# Power.net
KiCad netlist of a schematic drawn in Altium Designer
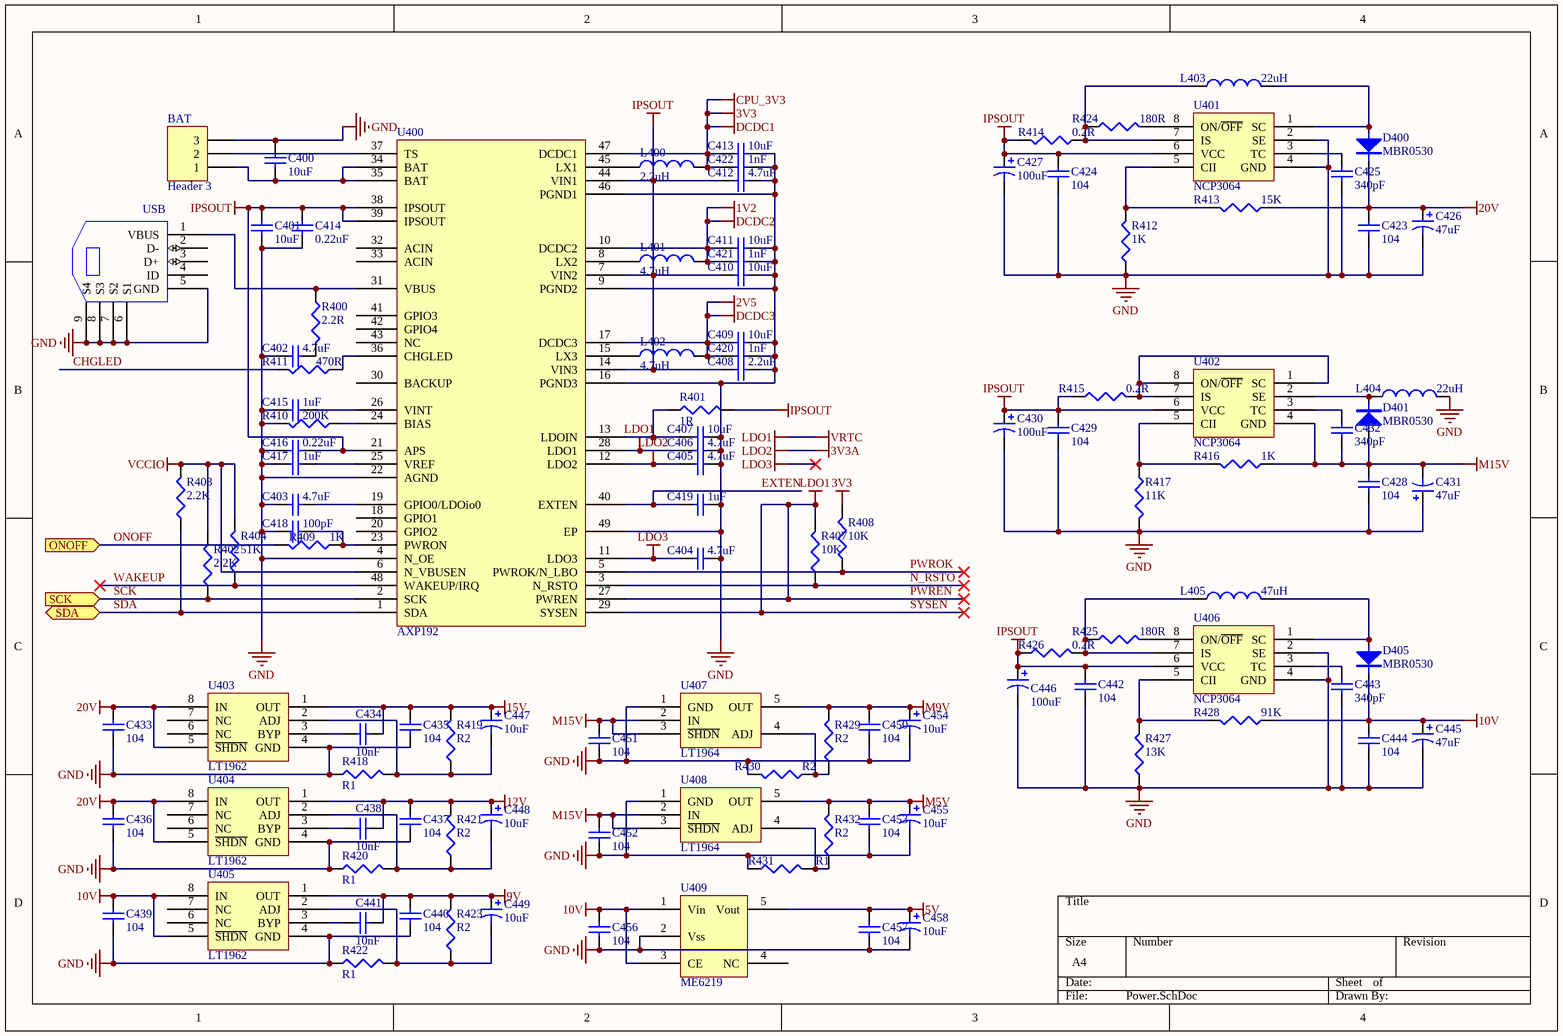
[diagram p0: Power.SchDoc]

(export (version "E")
  (design (tool "Eeschema 10.0.6"))
  (components
    (comp (ref "BAT")
      (value "Header 3")
      (footprint "LBAT")
      (description "Header, 3-Pin")
      (fields (field (name "PUBLISHER") "Altium Limited"))
      (libsource (lib "Miscellaneous Connectors") (part "Header 3"))
    )
    (comp (ref "C400")
      (value "10uF")
      (description "Capacitor (Semiconductor SIM Model)")
      (fields (field (name "PUBLISHER") "Altium Limited"))
      (libsource (lib "Miscellaneous Devices") (part "Cap Semi"))
    )
    (comp (ref "C401")
      (value "10uF")
      (description "Capacitor (Semiconductor SIM Model)")
      (fields (field (name "PUBLISHER") "Altium Limited"))
      (libsource (lib "Miscellaneous Devices") (part "Cap Semi"))
    )
    (comp (ref "C402")
      (value "4.7uF")
      (description "Capacitor (Semiconductor SIM Model)")
      (fields (field (name "PUBLISHER") "Altium Limited"))
      (libsource (lib "Miscellaneous Devices") (part "Cap Semi"))
    )
    (comp (ref "C403")
      (value "4.7uF")
      (description "Capacitor (Semiconductor SIM Model)")
      (fields (field (name "PUBLISHER") "Altium Limited"))
      (libsource (lib "Miscellaneous Devices") (part "Cap Semi"))
    )
    (comp (ref "C404")
      (value "4.7uF")
      (description "Capacitor (Semiconductor SIM Model)")
      (fields (field (name "PUBLISHER") "Altium Limited"))
      (libsource (lib "Miscellaneous Devices") (part "Cap Semi"))
    )
    (comp (ref "C405")
      (value "4.7uF")
      (description "Capacitor (Semiconductor SIM Model)")
      (fields (field (name "PUBLISHER") "Altium Limited"))
      (libsource (lib "Miscellaneous Devices") (part "Cap Semi"))
    )
    (comp (ref "C406")
      (value "4.7uF")
      (description "Capacitor (Semiconductor SIM Model)")
      (fields (field (name "PUBLISHER") "Altium Limited"))
      (libsource (lib "Miscellaneous Devices") (part "Cap Semi"))
    )
    (comp (ref "C407")
      (value "10uF")
      (description "Capacitor (Semiconductor SIM Model)")
      (fields (field (name "PUBLISHER") "Altium Limited"))
      (libsource (lib "Miscellaneous Devices") (part "Cap Semi"))
    )
    (comp (ref "C408")
      (value "2.2uF")
      (description "Capacitor (Semiconductor SIM Model)")
      (fields (field (name "PUBLISHER") "Altium Limited"))
      (libsource (lib "Miscellaneous Devices") (part "Cap Semi"))
    )
    (comp (ref "C409")
      (value "10uF")
      (description "Capacitor (Semiconductor SIM Model)")
      (fields (field (name "PUBLISHER") "Altium Limited"))
      (libsource (lib "Miscellaneous Devices") (part "Cap Semi"))
    )
    (comp (ref "C410")
      (value "10uF")
      (description "Capacitor (Semiconductor SIM Model)")
      (fields (field (name "PUBLISHER") "Altium Limited"))
      (libsource (lib "Miscellaneous Devices") (part "Cap Semi"))
    )
    (comp (ref "C411")
      (value "10uF")
      (description "Capacitor (Semiconductor SIM Model)")
      (fields (field (name "PUBLISHER") "Altium Limited"))
      (libsource (lib "Miscellaneous Devices") (part "Cap Semi"))
    )
    (comp (ref "C412")
      (value "4.7uF")
      (description "Capacitor (Semiconductor SIM Model)")
      (fields (field (name "PUBLISHER") "Altium Limited"))
      (libsource (lib "Miscellaneous Devices") (part "Cap Semi"))
    )
    (comp (ref "C413")
      (value "10uF")
      (description "Capacitor (Semiconductor SIM Model)")
      (fields (field (name "PUBLISHER") "Altium Limited"))
      (libsource (lib "Miscellaneous Devices") (part "Cap Semi"))
    )
    (comp (ref "C414")
      (value "0.22uF")
      (footprint "C0603")
      (description "Capacitor (Semiconductor SIM Model)")
      (fields (field (name "PUBLISHER") "Altium Limited"))
      (libsource (lib "Miscellaneous Devices") (part "Cap Semi"))
    )
    (comp (ref "C415")
      (value "1uF")
      (footprint "C0603")
      (description "Capacitor (Semiconductor SIM Model)")
      (fields (field (name "PUBLISHER") "Altium Limited"))
      (libsource (lib "Miscellaneous Devices") (part "Cap Semi"))
    )
    (comp (ref "C416")
      (value "0.22uF")
      (footprint "C0603")
      (description "Capacitor (Semiconductor SIM Model)")
      (fields (field (name "PUBLISHER") "Altium Limited"))
      (libsource (lib "Miscellaneous Devices") (part "Cap Semi"))
    )
    (comp (ref "C417")
      (value "1uF")
      (footprint "C0603")
      (description "Capacitor (Semiconductor SIM Model)")
      (fields (field (name "PUBLISHER") "Altium Limited"))
      (libsource (lib "Miscellaneous Devices") (part "Cap Semi"))
    )
    (comp (ref "C418")
      (value "100pF")
      (footprint "C0603")
      (description "Capacitor (Semiconductor SIM Model)")
      (fields (field (name "PUBLISHER") "Altium Limited"))
      (libsource (lib "Miscellaneous Devices") (part "Cap Semi"))
    )
    (comp (ref "C419")
      (value "1uF")
      (footprint "C0603")
      (description "Capacitor (Semiconductor SIM Model)")
      (fields (field (name "PUBLISHER") "Altium Limited"))
      (libsource (lib "Miscellaneous Devices") (part "Cap Semi"))
    )
    (comp (ref "C420")
      (value "1nF")
      (footprint "C0603")
      (description "Capacitor (Semiconductor SIM Model)")
      (fields (field (name "PUBLISHER") "Altium Limited"))
      (libsource (lib "Miscellaneous Devices") (part "Cap Semi"))
    )
    (comp (ref "C421")
      (value "1nF")
      (footprint "C0603")
      (description "Capacitor (Semiconductor SIM Model)")
      (fields (field (name "PUBLISHER") "Altium Limited"))
      (libsource (lib "Miscellaneous Devices") (part "Cap Semi"))
    )
    (comp (ref "C422")
      (value "1nF")
      (footprint "C0603")
      (description "Capacitor (Semiconductor SIM Model)")
      (fields (field (name "PUBLISHER") "Altium Limited"))
      (libsource (lib "Miscellaneous Devices") (part "Cap Semi"))
    )
    (comp (ref "C423")
      (value "104")
      (footprint "C0402")
      (description "Capacitor (Semiconductor SIM Model)")
      (fields (field (name "PUBLISHER") "Altium Limited"))
      (libsource (lib "Miscellaneous Devices") (part "Cap Semi"))
    )
    (comp (ref "C424")
      (value "104")
      (footprint "C0402")
      (description "Capacitor (Semiconductor SIM Model)")
      (fields (field (name "PUBLISHER") "Altium Limited"))
      (libsource (lib "Miscellaneous Devices") (part "Cap Semi"))
    )
    (comp (ref "C425")
      (value "340pF")
      (footprint "C0402")
      (description "Capacitor (Semiconductor SIM Model)")
      (fields (field (name "PUBLISHER") "Altium Limited"))
      (libsource (lib "Miscellaneous Devices") (part "Cap Semi"))
    )
    (comp (ref "C426")
      (value "47uF")
      (footprint "7343")
      (description "Polarized Capacitor (Radial)")
      (fields (field (name "PUBLISHER") "Altium Limited"))
      (libsource (lib "Miscellaneous Devices") (part "Cap Pol1"))
    )
    (comp (ref "C427")
      (value "100uF")
      (footprint "C0805")
      (description "Polarized Capacitor (Radial)")
      (fields (field (name "PUBLISHER") "Altium Limited"))
      (libsource (lib "Miscellaneous Devices") (part "Cap Pol1"))
    )
    (comp (ref "C428")
      (value "104")
      (footprint "C0402")
      (description "Capacitor (Semiconductor SIM Model)")
      (fields (field (name "PUBLISHER") "Altium Limited"))
      (libsource (lib "Miscellaneous Devices") (part "Cap Semi"))
    )
    (comp (ref "C429")
      (value "104")
      (footprint "C0402")
      (description "Capacitor (Semiconductor SIM Model)")
      (fields (field (name "PUBLISHER") "Altium Limited"))
      (libsource (lib "Miscellaneous Devices") (part "Cap Semi"))
    )
    (comp (ref "C430")
      (value "100uF")
      (footprint "C0805")
      (description "Polarized Capacitor (Radial)")
      (fields (field (name "PUBLISHER") "Altium Limited"))
      (libsource (lib "Miscellaneous Devices") (part "Cap Pol1"))
    )
    (comp (ref "C431")
      (value "47uF")
      (footprint "7343")
      (description "Polarized Capacitor (Radial)")
      (fields (field (name "PUBLISHER") "Altium Limited"))
      (libsource (lib "Miscellaneous Devices") (part "Cap Pol1"))
    )
    (comp (ref "C432")
      (value "340pF")
      (description "Capacitor (Semiconductor SIM Model)")
      (fields (field (name "PUBLISHER") "Altium Limited"))
      (libsource (lib "Miscellaneous Devices") (part "Cap Semi"))
    )
    (comp (ref "C433")
      (value "104")
      (footprint "C0402")
      (description "Capacitor (Semiconductor SIM Model)")
      (fields (field (name "PUBLISHER") "Altium Limited"))
      (libsource (lib "Miscellaneous Devices") (part "Cap Semi"))
    )
    (comp (ref "C434")
      (value "10nF")
      (footprint "C0402")
      (description "Capacitor (Semiconductor SIM Model)")
      (fields (field (name "PUBLISHER") "Altium Limited"))
      (libsource (lib "Miscellaneous Devices") (part "Cap Semi"))
    )
    (comp (ref "C435")
      (value "104")
      (footprint "C0402")
      (description "Capacitor (Semiconductor SIM Model)")
      (fields (field (name "PUBLISHER") "Altium Limited"))
      (libsource (lib "Miscellaneous Devices") (part "Cap Semi"))
    )
    (comp (ref "C436")
      (value "104")
      (footprint "C0402")
      (description "Capacitor (Semiconductor SIM Model)")
      (fields (field (name "PUBLISHER") "Altium Limited"))
      (libsource (lib "Miscellaneous Devices") (part "Cap Semi"))
    )
    (comp (ref "C437")
      (value "104")
      (footprint "C0402")
      (description "Capacitor (Semiconductor SIM Model)")
      (fields (field (name "PUBLISHER") "Altium Limited"))
      (libsource (lib "Miscellaneous Devices") (part "Cap Semi"))
    )
    (comp (ref "C438")
      (value "10nF")
      (footprint "C0402")
      (description "Capacitor (Semiconductor SIM Model)")
      (fields (field (name "PUBLISHER") "Altium Limited"))
      (libsource (lib "Miscellaneous Devices") (part "Cap Semi"))
    )
    (comp (ref "C439")
      (value "104")
      (footprint "C0402")
      (description "Capacitor (Semiconductor SIM Model)")
      (fields (field (name "PUBLISHER") "Altium Limited"))
      (libsource (lib "Miscellaneous Devices") (part "Cap Semi"))
    )
    (comp (ref "C440")
      (value "104")
      (footprint "C0402")
      (description "Capacitor (Semiconductor SIM Model)")
      (fields (field (name "PUBLISHER") "Altium Limited"))
      (libsource (lib "Miscellaneous Devices") (part "Cap Semi"))
    )
    (comp (ref "C441")
      (value "10nF")
      (footprint "C0402")
      (description "Capacitor (Semiconductor SIM Model)")
      (fields (field (name "PUBLISHER") "Altium Limited"))
      (libsource (lib "Miscellaneous Devices") (part "Cap Semi"))
    )
    (comp (ref "C442")
      (value "104")
      (footprint "C0402")
      (description "Capacitor (Semiconductor SIM Model)")
      (fields (field (name "PUBLISHER") "Altium Limited"))
      (libsource (lib "Miscellaneous Devices") (part "Cap Semi"))
    )
    (comp (ref "C443")
      (value "340pF")
      (footprint "C0402")
      (description "Capacitor (Semiconductor SIM Model)")
      (fields (field (name "PUBLISHER") "Altium Limited"))
      (libsource (lib "Miscellaneous Devices") (part "Cap Semi"))
    )
    (comp (ref "C444")
      (value "104")
      (footprint "C0402")
      (description "Capacitor (Semiconductor SIM Model)")
      (fields (field (name "PUBLISHER") "Altium Limited"))
      (libsource (lib "Miscellaneous Devices") (part "Cap Semi"))
    )
    (comp (ref "C445")
      (value "47uF")
      (footprint "7343")
      (description "Polarized Capacitor (Radial)")
      (fields (field (name "PUBLISHER") "Altium Limited"))
      (libsource (lib "Miscellaneous Devices") (part "Cap Pol1"))
    )
    (comp (ref "C446")
      (value "100uF")
      (footprint "C0805")
      (description "Polarized Capacitor (Radial)")
      (fields (field (name "PUBLISHER") "Altium Limited"))
      (libsource (lib "Miscellaneous Devices") (part "Cap Pol1"))
    )
    (comp (ref "C447")
      (value "10uF")
      (footprint "7343")
      (description "Polarized Capacitor (Radial)")
      (fields (field (name "PUBLISHER") "Altium Limited"))
      (libsource (lib "Miscellaneous Devices") (part "Cap Pol1"))
    )
    (comp (ref "C448")
      (value "10uF")
      (footprint "7343")
      (description "Polarized Capacitor (Radial)")
      (fields (field (name "PUBLISHER") "Altium Limited"))
      (libsource (lib "Miscellaneous Devices") (part "Cap Pol1"))
    )
    (comp (ref "C449")
      (value "10uF")
      (footprint "7343")
      (description "Polarized Capacitor (Radial)")
      (fields (field (name "PUBLISHER") "Altium Limited"))
      (libsource (lib "Miscellaneous Devices") (part "Cap Pol1"))
    )
    (comp (ref "C450")
      (value "104")
      (footprint "C0402")
      (description "Capacitor (Semiconductor SIM Model)")
      (fields (field (name "PUBLISHER") "Altium Limited"))
      (libsource (lib "Miscellaneous Devices") (part "Cap Semi"))
    )
    (comp (ref "C451")
      (value "104")
      (footprint "C0402")
      (description "Capacitor (Semiconductor SIM Model)")
      (fields (field (name "PUBLISHER") "Altium Limited"))
      (libsource (lib "Miscellaneous Devices") (part "Cap Semi"))
    )
    (comp (ref "C452")
      (value "104")
      (footprint "C0402")
      (description "Capacitor (Semiconductor SIM Model)")
      (fields (field (name "PUBLISHER") "Altium Limited"))
      (libsource (lib "Miscellaneous Devices") (part "Cap Semi"))
    )
    (comp (ref "C453")
      (value "104")
      (footprint "C0402")
      (description "Capacitor (Semiconductor SIM Model)")
      (fields (field (name "PUBLISHER") "Altium Limited"))
      (libsource (lib "Miscellaneous Devices") (part "Cap Semi"))
    )
    (comp (ref "C454")
      (value "10uF")
      (footprint "7343")
      (description "Polarized Capacitor (Radial)")
      (fields (field (name "PUBLISHER") "Altium Limited"))
      (libsource (lib "Miscellaneous Devices") (part "Cap Pol1"))
    )
    (comp (ref "C455")
      (value "10uF")
      (footprint "7343")
      (description "Polarized Capacitor (Radial)")
      (fields (field (name "PUBLISHER") "Altium Limited"))
      (libsource (lib "Miscellaneous Devices") (part "Cap Pol1"))
    )
    (comp (ref "C456")
      (value "104")
      (footprint "C0402")
      (description "Capacitor (Semiconductor SIM Model)")
      (fields (field (name "PUBLISHER") "Altium Limited"))
      (libsource (lib "Miscellaneous Devices") (part "Cap Semi"))
    )
    (comp (ref "C457")
      (value "104")
      (footprint "C0402")
      (description "Capacitor (Semiconductor SIM Model)")
      (fields (field (name "PUBLISHER") "Altium Limited"))
      (libsource (lib "Miscellaneous Devices") (part "Cap Semi"))
    )
    (comp (ref "C458")
      (value "10uF")
      (footprint "7343")
      (description "Polarized Capacitor (Radial)")
      (fields (field (name "PUBLISHER") "Altium Limited"))
      (libsource (lib "Miscellaneous Devices") (part "Cap Pol1"))
    )
    (comp (ref "D400") (value "MBR0530") (footprint "SOD123") (libsource (lib "Schlib1") (part "MBR0530")))
    (comp (ref "D401") (value "MBR0530") (footprint "SOD123") (libsource (lib "Schlib1") (part "MBR0530")))
    (comp (ref "D405") (value "MBR0530") (footprint "SOD123") (libsource (lib "Schlib1") (part "MBR0530")))
    (comp (ref "L400")
      (value "2.2uH")
      (footprint "IND_4X4")
      (description "Inductor")
      (fields (field (name "PUBLISHER") "Altium Limited"))
      (libsource (lib "Miscellaneous Devices") (part "Inductor"))
    )
    (comp (ref "L401")
      (value "4.7uH")
      (footprint "IND_4X4")
      (description "Inductor")
      (fields (field (name "PUBLISHER") "Altium Limited"))
      (libsource (lib "Miscellaneous Devices") (part "Inductor"))
    )
    (comp (ref "L402")
      (value "4.7uH")
      (footprint "IND_4X4")
      (description "Inductor")
      (fields (field (name "PUBLISHER") "Altium Limited"))
      (libsource (lib "Miscellaneous Devices") (part "Inductor"))
    )
    (comp (ref "L403")
      (value "22uH")
      (footprint "IND_4X4")
      (description "Inductor")
      (fields (field (name "PUBLISHER") "Altium Limited"))
      (libsource (lib "Miscellaneous Devices") (part "Inductor"))
    )
    (comp (ref "L404")
      (value "22uH")
      (footprint "IND_4X4")
      (description "Inductor")
      (fields (field (name "PUBLISHER") "Altium Limited"))
      (libsource (lib "Miscellaneous Devices") (part "Inductor"))
    )
    (comp (ref "L405")
      (value "47uH")
      (footprint "IND_4X4")
      (description "Inductor")
      (fields (field (name "PUBLISHER") "Altium Limited"))
      (libsource (lib "Miscellaneous Devices") (part "Inductor"))
    )
    (comp (ref "R400")
      (value "2.2R")
      (footprint "R0603")
      (description "Resistor")
      (fields (field (name "PUBLISHER") "Altium Limited"))
      (libsource (lib "Miscellaneous Devices") (part "Res3"))
    )
    (comp (ref "R401")
      (value "1R")
      (footprint "R0805")
      (description "Resistor")
      (fields (field (name "PUBLISHER") "Altium Limited"))
      (libsource (lib "Miscellaneous Devices") (part "Res3"))
    )
    (comp (ref "R402")
      (value "2.2K")
      (footprint "R0603")
      (description "Resistor")
      (fields (field (name "PUBLISHER") "Altium Limited"))
      (libsource (lib "Miscellaneous Devices") (part "Res3"))
    )
    (comp (ref "R403")
      (value "2.2K")
      (footprint "R0603")
      (description "Resistor")
      (fields (field (name "PUBLISHER") "Altium Limited"))
      (libsource (lib "Miscellaneous Devices") (part "Res3"))
    )
    (comp (ref "R404")
      (value "51K")
      (footprint "R0603")
      (description "Resistor")
      (fields (field (name "PUBLISHER") "Altium Limited"))
      (libsource (lib "Miscellaneous Devices") (part "Res3"))
    )
    (comp (ref "R407")
      (value "10K")
      (footprint "R0603")
      (description "Resistor")
      (fields (field (name "PUBLISHER") "Altium Limited"))
      (libsource (lib "Miscellaneous Devices") (part "Res3"))
    )
    (comp (ref "R408")
      (value "10K")
      (footprint "R0603")
      (description "Resistor")
      (fields (field (name "PUBLISHER") "Altium Limited"))
      (libsource (lib "Miscellaneous Devices") (part "Res3"))
    )
    (comp (ref "R409")
      (value "1K")
      (footprint "R0603")
      (description "Resistor")
      (fields (field (name "PUBLISHER") "Altium Limited"))
      (libsource (lib "Miscellaneous Devices") (part "Res3"))
    )
    (comp (ref "R410")
      (value "200K")
      (footprint "R0603")
      (description "Resistor")
      (fields (field (name "PUBLISHER") "Altium Limited"))
      (libsource (lib "Miscellaneous Devices") (part "Res3"))
    )
    (comp (ref "R411")
      (value "470R")
      (footprint "R0603")
      (description "Resistor")
      (fields (field (name "PUBLISHER") "Altium Limited"))
      (libsource (lib "Miscellaneous Devices") (part "Res3"))
    )
    (comp (ref "R412")
      (value "1K")
      (footprint "R0603")
      (description "Resistor")
      (fields (field (name "PUBLISHER") "Altium Limited"))
      (libsource (lib "Miscellaneous Devices") (part "Res3"))
    )
    (comp (ref "R413")
      (value "15K")
      (footprint "R0603")
      (description "Resistor")
      (fields (field (name "PUBLISHER") "Altium Limited"))
      (libsource (lib "Miscellaneous Devices") (part "Res3"))
    )
    (comp (ref "R414")
      (value "0.2R")
      (footprint "R0805")
      (description "Resistor")
      (fields (field (name "PUBLISHER") "Altium Limited"))
      (libsource (lib "Miscellaneous Devices") (part "Res3"))
    )
    (comp (ref "R415")
      (value "0.2R")
      (footprint "R0805")
      (description "Resistor")
      (fields (field (name "PUBLISHER") "Altium Limited"))
      (libsource (lib "Miscellaneous Devices") (part "Res3"))
    )
    (comp (ref "R416")
      (value "1K")
      (footprint "R0603")
      (description "Resistor")
      (fields (field (name "PUBLISHER") "Altium Limited"))
      (libsource (lib "Miscellaneous Devices") (part "Res3"))
    )
    (comp (ref "R417")
      (value "11K")
      (footprint "R0603")
      (description "Resistor")
      (fields (field (name "PUBLISHER") "Altium Limited"))
      (libsource (lib "Miscellaneous Devices") (part "Res3"))
    )
    (comp (ref "R418")
      (value "R1")
      (footprint "R0603")
      (description "Resistor")
      (fields (field (name "PUBLISHER") "Altium Limited"))
      (libsource (lib "Miscellaneous Devices") (part "Res3"))
    )
    (comp (ref "R419")
      (value "R2")
      (footprint "R0603")
      (description "Resistor")
      (fields (field (name "PUBLISHER") "Altium Limited"))
      (libsource (lib "Miscellaneous Devices") (part "Res3"))
    )
    (comp (ref "R420")
      (value "R1")
      (footprint "R0603")
      (description "Resistor")
      (fields (field (name "PUBLISHER") "Altium Limited"))
      (libsource (lib "Miscellaneous Devices") (part "Res3"))
    )
    (comp (ref "R421")
      (value "R2")
      (footprint "R0603")
      (description "Resistor")
      (fields (field (name "PUBLISHER") "Altium Limited"))
      (libsource (lib "Miscellaneous Devices") (part "Res3"))
    )
    (comp (ref "R422")
      (value "R1")
      (footprint "R0603")
      (description "Resistor")
      (fields (field (name "PUBLISHER") "Altium Limited"))
      (libsource (lib "Miscellaneous Devices") (part "Res3"))
    )
    (comp (ref "R423")
      (value "R2")
      (footprint "R0603")
      (description "Resistor")
      (fields (field (name "PUBLISHER") "Altium Limited"))
      (libsource (lib "Miscellaneous Devices") (part "Res3"))
    )
    (comp (ref "R424")
      (value "180R")
      (footprint "R0603")
      (description "Resistor")
      (fields (field (name "PUBLISHER") "Altium Limited"))
      (libsource (lib "Miscellaneous Devices") (part "Res3"))
    )
    (comp (ref "R425")
      (value "180R")
      (footprint "R0603")
      (description "Resistor")
      (fields (field (name "PUBLISHER") "Altium Limited"))
      (libsource (lib "Miscellaneous Devices") (part "Res3"))
    )
    (comp (ref "R426")
      (value "0.2R")
      (footprint "R0805")
      (description "Resistor")
      (fields (field (name "PUBLISHER") "Altium Limited"))
      (libsource (lib "Miscellaneous Devices") (part "Res3"))
    )
    (comp (ref "R427")
      (value "13K")
      (footprint "R0603")
      (description "Resistor")
      (fields (field (name "PUBLISHER") "Altium Limited"))
      (libsource (lib "Miscellaneous Devices") (part "Res3"))
    )
    (comp (ref "R428")
      (value "91K")
      (footprint "R0603")
      (description "Resistor")
      (fields (field (name "PUBLISHER") "Altium Limited"))
      (libsource (lib "Miscellaneous Devices") (part "Res3"))
    )
    (comp (ref "R429")
      (value "R2")
      (footprint "R0603")
      (description "Resistor")
      (fields (field (name "PUBLISHER") "Altium Limited"))
      (libsource (lib "Miscellaneous Devices") (part "Res3"))
    )
    (comp (ref "R430")
      (value "R2")
      (footprint "R0603")
      (description "Resistor")
      (fields (field (name "PUBLISHER") "Altium Limited"))
      (libsource (lib "Miscellaneous Devices") (part "Res3"))
    )
    (comp (ref "R431")
      (value "R1")
      (footprint "R0603")
      (description "Resistor")
      (fields (field (name "PUBLISHER") "Altium Limited"))
      (libsource (lib "Miscellaneous Devices") (part "Res3"))
    )
    (comp (ref "R432")
      (value "R2")
      (footprint "R0603")
      (description "Resistor")
      (fields (field (name "PUBLISHER") "Altium Limited"))
      (libsource (lib "Miscellaneous Devices") (part "Res3"))
    )
    (comp (ref "U400") (value "AXP192") (footprint "QFN-48") (libsource (lib "Schlib1") (part "AXP192")))
    (comp (ref "U401") (value "NCP3064") (footprint "SOP-8") (libsource (lib "Schlib1") (part "NCP3064")))
    (comp (ref "U402") (value "NCP3064") (footprint "SOP-8") (libsource (lib "Schlib1") (part "NCP3064")))
    (comp (ref "U403") (value "LT1962") (footprint "MS8") (libsource (lib "Schlib1") (part "LT1962")))
    (comp (ref "U404") (value "LT1962") (footprint "MS8") (libsource (lib "Schlib1") (part "LT1962")))
    (comp (ref "U405") (value "LT1962") (footprint "MS8") (libsource (lib "Schlib1") (part "LT1962")))
    (comp (ref "U406") (value "NCP3064") (footprint "SOP-8") (libsource (lib "Schlib1") (part "NCP3064")))
    (comp (ref "U407") (value "LT1964") (footprint "SOT25") (libsource (lib "Schlib1") (part "LT1964")))
    (comp (ref "U408") (value "LT1964") (footprint "SOT25") (libsource (lib "Schlib1") (part "LT1964")))
    (comp (ref "U409") (value "ME6219") (footprint "SOT25") (libsource (lib "Schlib1") (part "ME6219")))
    (comp (ref "USB")
      (value "USB-MICRO")
      (footprint "HUM011D-5-S")
      (libsource (lib "Schlib1") (part "USB-MICRO"))
    )
  )
  (nets
    (net (code "1") (name "/CHGLED") (class "Default")
      (node (ref "R411") (pin "2") (pinfunction "2_2") (pintype "passive"))
    )
    (net (code "2") (name "/EXTEN") (class "Default")
      (node (ref "C419") (pin "2") (pinfunction "2_2") (pintype "passive"))
      (node (ref "U400") (pin "40") (pinfunction "EXTEN_40") (pintype "passive"))
    )
    (net (code "3") (name "/N_RSTO") (class "Default")
      (node (ref "R407") (pin "1") (pinfunction "1_1") (pintype "passive"))
      (node (ref "U400") (pin "3") (pinfunction "N_RSTO_3") (pintype "passive"))
    )
    (net (code "4") (name "/ONOFF") (class "Default")
      (node (ref "R409") (pin "2") (pinfunction "2_2") (pintype "passive"))
    )
    (net (code "5") (name "/PWROK") (class "Default")
      (node (ref "R408") (pin "1") (pinfunction "1_1") (pintype "passive"))
      (node (ref "U400") (pin "5") (pinfunction "PWROK/N_LBO_5") (pintype "passive"))
    )
    (net (code "6") (name "/SCK") (class "Default")
      (node (ref "R402") (pin "1") (pinfunction "1_1") (pintype "passive"))
      (node (ref "U400") (pin "2") (pinfunction "SCK_2") (pintype "passive"))
    )
    (net (code "7") (name "/SDA") (class "Default")
      (node (ref "R403") (pin "1") (pinfunction "1_1") (pintype "passive"))
      (node (ref "U400") (pin "1") (pinfunction "SDA_1") (pintype "passive"))
    )
    (net (code "8") (name "/WAKEUP") (class "Default")
      (node (ref "R404") (pin "1") (pinfunction "1_1") (pintype "passive"))
      (node (ref "U400") (pin "48") (pinfunction "WAKEUP/IRQ_48") (pintype "passive"))
    )
    (net (code "9") (name "1V2") (class "Default")
      (node (ref "C411") (pin "1") (pinfunction "1_1") (pintype "passive"))
      (node (ref "C421") (pin "2") (pinfunction "2_2") (pintype "passive"))
      (node (ref "L401") (pin "2") (pinfunction "2_2") (pintype "passive"))
      (node (ref "U400") (pin "10") (pinfunction "DCDC2_10") (pintype "passive"))
    )
    (net (code "10") (name "2V5") (class "Default")
      (node (ref "C409") (pin "1") (pinfunction "1_1") (pintype "passive"))
      (node (ref "C420") (pin "2") (pinfunction "2_2") (pintype "passive"))
      (node (ref "L402") (pin "2") (pinfunction "2_2") (pintype "passive"))
      (node (ref "U400") (pin "17") (pinfunction "DCDC3_17") (pintype "passive"))
    )
    (net (code "11") (name "3V3") (class "Default")
      (node (ref "C413") (pin "1") (pinfunction "1_1") (pintype "passive"))
      (node (ref "C422") (pin "2") (pinfunction "2_2") (pintype "passive"))
      (node (ref "L400") (pin "2") (pinfunction "2_2") (pintype "passive"))
      (node (ref "R408") (pin "2") (pinfunction "2_2") (pintype "passive"))
      (node (ref "U400") (pin "47") (pinfunction "DCDC1_47") (pintype "passive"))
    )
    (net (code "12") (name "3V3A") (class "Default")
      (node (ref "C405") (pin "1") (pinfunction "1_1") (pintype "passive"))
      (node (ref "U400") (pin "12") (pinfunction "LDO2_12") (pintype "passive"))
    )
    (net (code "13") (name "5V") (class "Default")
      (node (ref "C457") (pin "2") (pinfunction "2_2") (pintype "passive"))
      (node (ref "C458") (pin "1") (pinfunction "1_1") (pintype "passive"))
      (node (ref "U409") (pin "5") (pinfunction "Vout_5") (pintype "passive"))
    )
    (net (code "14") (name "9V") (class "Default")
      (node (ref "C440") (pin "2") (pinfunction "2_2") (pintype "passive"))
      (node (ref "C441") (pin "1") (pinfunction "1_1") (pintype "passive"))
      (node (ref "C449") (pin "1") (pinfunction "1_1") (pintype "passive"))
      (node (ref "R423") (pin "2") (pinfunction "2_2") (pintype "passive"))
      (node (ref "U405") (pin "1") (pinfunction "OUT_1") (pintype "passive"))
    )
    (net (code "15") (name "10V") (class "Default")
      (node (ref "C439") (pin "2") (pinfunction "2_2") (pintype "passive"))
      (node (ref "C444") (pin "1") (pinfunction "1_1") (pintype "passive"))
      (node (ref "C445") (pin "1") (pinfunction "1_1") (pintype "passive"))
      (node (ref "C456") (pin "2") (pinfunction "2_2") (pintype "passive"))
      (node (ref "D405") (pin "2") (pinfunction "2_2") (pintype "passive"))
      (node (ref "R428") (pin "1") (pinfunction "1_1") (pintype "passive"))
      (node (ref "U405") (pin "5") (pinfunction "~{SHDN}_5") (pintype "passive"))
      (node (ref "U405") (pin "8") (pinfunction "IN_8") (pintype "passive"))
      (node (ref "U409") (pin "1") (pinfunction "Vin_1") (pintype "passive"))
      (node (ref "U409") (pin "3") (pinfunction "CE_3") (pintype "passive"))
    )
    (net (code "16") (name "12V") (class "Default")
      (node (ref "C437") (pin "1") (pinfunction "1_1") (pintype "passive"))
      (node (ref "C438") (pin "2") (pinfunction "2_2") (pintype "passive"))
      (node (ref "C448") (pin "1") (pinfunction "1_1") (pintype "passive"))
      (node (ref "R421") (pin "2") (pinfunction "2_2") (pintype "passive"))
      (node (ref "U404") (pin "1") (pinfunction "OUT_1") (pintype "passive"))
    )
    (net (code "17") (name "15V") (class "Default")
      (node (ref "C434") (pin "1") (pinfunction "1_1") (pintype "passive"))
      (node (ref "C435") (pin "1") (pinfunction "1_1") (pintype "passive"))
      (node (ref "C447") (pin "1") (pinfunction "1_1") (pintype "passive"))
      (node (ref "R419") (pin "2") (pinfunction "2_2") (pintype "passive"))
      (node (ref "U403") (pin "1") (pinfunction "OUT_1") (pintype "passive"))
    )
    (net (code "18") (name "20V") (class "Default")
      (node (ref "C423") (pin "2") (pinfunction "2_2") (pintype "passive"))
      (node (ref "C426") (pin "1") (pinfunction "1_1") (pintype "passive"))
      (node (ref "C433") (pin "2") (pinfunction "2_2") (pintype "passive"))
      (node (ref "C436") (pin "1") (pinfunction "1_1") (pintype "passive"))
      (node (ref "D400") (pin "2") (pinfunction "2_2") (pintype "passive"))
      (node (ref "R413") (pin "1") (pinfunction "1_1") (pintype "passive"))
      (node (ref "U403") (pin "5") (pinfunction "~{SHDN}_5") (pintype "passive"))
      (node (ref "U403") (pin "8") (pinfunction "IN_8") (pintype "passive"))
      (node (ref "U404") (pin "5") (pinfunction "~{SHDN}_5") (pintype "passive"))
      (node (ref "U404") (pin "8") (pinfunction "IN_8") (pintype "passive"))
    )
    (net (code "19") (name "GND") (class "Default")
      (node (ref "BAT") (pin "3") (pinfunction "3_3") (pintype "passive"))
      (node (ref "C400") (pin "2") (pinfunction "2_2") (pintype "passive"))
      (node (ref "C401") (pin "1") (pinfunction "1_1") (pintype "passive"))
      (node (ref "C402") (pin "2") (pinfunction "2_2") (pintype "passive"))
      (node (ref "C403") (pin "1") (pinfunction "1_1") (pintype "passive"))
      (node (ref "C404") (pin "1") (pinfunction "1_1") (pintype "passive"))
      (node (ref "C405") (pin "2") (pinfunction "2_2") (pintype "passive"))
      (node (ref "C406") (pin "2") (pinfunction "2_2") (pintype "passive"))
      (node (ref "C407") (pin "2") (pinfunction "2_2") (pintype "passive"))
      (node (ref "C408") (pin "2") (pinfunction "2_2") (pintype "passive"))
      (node (ref "C409") (pin "2") (pinfunction "2_2") (pintype "passive"))
      (node (ref "C410") (pin "2") (pinfunction "2_2") (pintype "passive"))
      (node (ref "C411") (pin "2") (pinfunction "2_2") (pintype "passive"))
      (node (ref "C412") (pin "2") (pinfunction "2_2") (pintype "passive"))
      (node (ref "C413") (pin "2") (pinfunction "2_2") (pintype "passive"))
      (node (ref "C414") (pin "1") (pinfunction "1_1") (pintype "passive"))
      (node (ref "C415") (pin "2") (pinfunction "2_2") (pintype "passive"))
      (node (ref "C416") (pin "2") (pinfunction "2_2") (pintype "passive"))
      (node (ref "C417") (pin "2") (pinfunction "2_2") (pintype "passive"))
      (node (ref "C418") (pin "2") (pinfunction "2_2") (pintype "passive"))
      (node (ref "C419") (pin "1") (pinfunction "1_1") (pintype "passive"))
      (node (ref "C420") (pin "1") (pinfunction "1_1") (pintype "passive"))
      (node (ref "C421") (pin "1") (pinfunction "1_1") (pintype "passive"))
      (node (ref "C422") (pin "1") (pinfunction "1_1") (pintype "passive"))
      (node (ref "C423") (pin "1") (pinfunction "1_1") (pintype "passive"))
      (node (ref "C424") (pin "1") (pinfunction "1_1") (pintype "passive"))
      (node (ref "C425") (pin "1") (pinfunction "1_1") (pintype "passive"))
      (node (ref "C426") (pin "2") (pinfunction "2_2") (pintype "passive"))
      (node (ref "C427") (pin "2") (pinfunction "2_2") (pintype "passive"))
      (node (ref "C428") (pin "1") (pinfunction "1_1") (pintype "passive"))
      (node (ref "C429") (pin "1") (pinfunction "1_1") (pintype "passive"))
      (node (ref "C430") (pin "2") (pinfunction "2_2") (pintype "passive"))
      (node (ref "C431") (pin "1") (pinfunction "1_1") (pintype "passive"))
      (node (ref "C433") (pin "1") (pinfunction "1_1") (pintype "passive"))
      (node (ref "C435") (pin "2") (pinfunction "2_2") (pintype "passive"))
      (node (ref "C436") (pin "2") (pinfunction "2_2") (pintype "passive"))
      (node (ref "C437") (pin "2") (pinfunction "2_2") (pintype "passive"))
      (node (ref "C439") (pin "1") (pinfunction "1_1") (pintype "passive"))
      (node (ref "C440") (pin "1") (pinfunction "1_1") (pintype "passive"))
      (node (ref "C442") (pin "2") (pinfunction "2_2") (pintype "passive"))
      (node (ref "C443") (pin "2") (pinfunction "2_2") (pintype "passive"))
      (node (ref "C444") (pin "2") (pinfunction "2_2") (pintype "passive"))
      (node (ref "C445") (pin "2") (pinfunction "2_2") (pintype "passive"))
      (node (ref "C446") (pin "2") (pinfunction "2_2") (pintype "passive"))
      (node (ref "C450") (pin "1") (pinfunction "1_1") (pintype "passive"))
      (node (ref "C451") (pin "1") (pinfunction "1_1") (pintype "passive"))
      (node (ref "C452") (pin "1") (pinfunction "1_1") (pintype "passive"))
      (node (ref "C453") (pin "1") (pinfunction "1_1") (pintype "passive"))
      (node (ref "C454") (pin "2") (pinfunction "2_2") (pintype "passive"))
      (node (ref "C455") (pin "2") (pinfunction "2_2") (pintype "passive"))
      (node (ref "C456") (pin "1") (pinfunction "1_1") (pintype "passive"))
      (node (ref "C457") (pin "1") (pinfunction "1_1") (pintype "passive"))
      (node (ref "C458") (pin "2") (pinfunction "2_2") (pintype "passive"))
      (node (ref "L404") (pin "2") (pinfunction "2_2") (pintype "passive"))
      (node (ref "R410") (pin "2") (pinfunction "2_2") (pintype "passive"))
      (node (ref "R412") (pin "1") (pinfunction "1_1") (pintype "passive"))
      (node (ref "R417") (pin "2") (pinfunction "2_2") (pintype "passive"))
      (node (ref "R418") (pin "1") (pinfunction "1_1") (pintype "passive"))
      (node (ref "R420") (pin "1") (pinfunction "1_1") (pintype "passive"))
      (node (ref "R422") (pin "1") (pinfunction "1_1") (pintype "passive"))
      (node (ref "R427") (pin "1") (pinfunction "1_1") (pintype "passive"))
      (node (ref "R430") (pin "2") (pinfunction "2_2") (pintype "passive"))
      (node (ref "R431") (pin "1") (pinfunction "1_1") (pintype "passive"))
      (node (ref "U400") (pin "16") (pinfunction "PGND3_16") (pintype "passive"))
      (node (ref "U400") (pin "22") (pinfunction "AGND_22") (pintype "passive"))
      (node (ref "U400") (pin "4") (pinfunction "N_OE_4") (pintype "passive"))
      (node (ref "U400") (pin "46") (pinfunction "PGND1_46") (pintype "passive"))
      (node (ref "U400") (pin "49") (pinfunction "EP_49") (pintype "passive"))
      (node (ref "U400") (pin "9") (pinfunction "PGND2_9") (pintype "passive"))
      (node (ref "U401") (pin "2") (pinfunction "SE_2") (pintype "passive"))
      (node (ref "U401") (pin "4") (pinfunction "GND_4") (pintype "passive"))
      (node (ref "U403") (pin "4") (pinfunction "GND_4") (pintype "passive"))
      (node (ref "U404") (pin "4") (pinfunction "GND_4") (pintype "passive"))
      (node (ref "U405") (pin "4") (pinfunction "GND_4") (pintype "passive"))
      (node (ref "U406") (pin "2") (pinfunction "SE_2") (pintype "passive"))
      (node (ref "U406") (pin "4") (pinfunction "GND_4") (pintype "passive"))
      (node (ref "U407") (pin "1") (pinfunction "GND_1") (pintype "passive"))
      (node (ref "U408") (pin "1") (pinfunction "GND_1") (pintype "passive"))
      (node (ref "U409") (pin "2") (pinfunction "Vss_2") (pintype "passive"))
      (node (ref "USB") (pin "5") (pinfunction "GND_5") (pintype "power_in"))
      (node (ref "USB") (pin "6") (pinfunction "S1_6") (pintype "passive"))
      (node (ref "USB") (pin "7") (pinfunction "S2_7") (pintype "passive"))
      (node (ref "USB") (pin "8") (pinfunction "S3_8") (pintype "passive"))
      (node (ref "USB") (pin "9") (pinfunction "S4_9") (pintype "passive"))
    )
    (net (code "20") (name "IPSOUT") (class "Default")
      (node (ref "C401") (pin "2") (pinfunction "2_2") (pintype "passive"))
      (node (ref "C408") (pin "1") (pinfunction "1_1") (pintype "passive"))
      (node (ref "C410") (pin "1") (pinfunction "1_1") (pintype "passive"))
      (node (ref "C412") (pin "1") (pinfunction "1_1") (pintype "passive"))
      (node (ref "C414") (pin "2") (pinfunction "2_2") (pintype "passive"))
      (node (ref "C416") (pin "1") (pinfunction "1_1") (pintype "passive"))
      (node (ref "C424") (pin "2") (pinfunction "2_2") (pintype "passive"))
      (node (ref "C427") (pin "1") (pinfunction "1_1") (pintype "passive"))
      (node (ref "C429") (pin "2") (pinfunction "2_2") (pintype "passive"))
      (node (ref "C430") (pin "1") (pinfunction "1_1") (pintype "passive"))
      (node (ref "C442") (pin "1") (pinfunction "1_1") (pintype "passive"))
      (node (ref "C446") (pin "1") (pinfunction "1_1") (pintype "passive"))
      (node (ref "R401") (pin "2") (pinfunction "2_2") (pintype "passive"))
      (node (ref "R414") (pin "2") (pinfunction "2_2") (pintype "passive"))
      (node (ref "R415") (pin "1") (pinfunction "1_1") (pintype "passive"))
      (node (ref "R426") (pin "1") (pinfunction "1_1") (pintype "passive"))
      (node (ref "U400") (pin "14") (pinfunction "VIN3_14") (pintype "passive"))
      (node (ref "U400") (pin "21") (pinfunction "APS_21") (pintype "passive"))
      (node (ref "U400") (pin "38") (pinfunction "IPSOUT_38") (pintype "passive"))
      (node (ref "U400") (pin "39") (pinfunction "IPSOUT_39") (pintype "passive"))
      (node (ref "U400") (pin "44") (pinfunction "VIN1_44") (pintype "passive"))
      (node (ref "U400") (pin "7") (pinfunction "VIN2_7") (pintype "passive"))
      (node (ref "U401") (pin "6") (pinfunction "VCC_6") (pintype "passive"))
      (node (ref "U402") (pin "6") (pinfunction "VCC_6") (pintype "passive"))
      (node (ref "U406") (pin "6") (pinfunction "VCC_6") (pintype "passive"))
    )
    (net (code "21") (name "LDO1") (class "Default")
      (node (ref "C406") (pin "1") (pinfunction "1_1") (pintype "passive"))
      (node (ref "R407") (pin "2") (pinfunction "2_2") (pintype "passive"))
      (node (ref "U400") (pin "27") (pinfunction "PWREN_27") (pintype "passive"))
      (node (ref "U400") (pin "28") (pinfunction "LDO1_28") (pintype "passive"))
      (node (ref "U400") (pin "29") (pinfunction "SYSEN_29") (pintype "passive"))
    )
    (net (code "22") (name "LDO3") (class "Default")
      (node (ref "C404") (pin "2") (pinfunction "2_2") (pintype "passive"))
      (node (ref "U400") (pin "11") (pinfunction "LDO3_11") (pintype "passive"))
    )
    (net (code "23") (name "M5V") (class "Default")
      (node (ref "C453") (pin "2") (pinfunction "2_2") (pintype "passive"))
      (node (ref "C455") (pin "1") (pinfunction "1_1") (pintype "passive"))
      (node (ref "R432") (pin "2") (pinfunction "2_2") (pintype "passive"))
      (node (ref "U408") (pin "5") (pinfunction "OUT_5") (pintype "passive"))
    )
    (net (code "24") (name "M9V") (class "Default")
      (node (ref "C450") (pin "2") (pinfunction "2_2") (pintype "passive"))
      (node (ref "C454") (pin "1") (pinfunction "1_1") (pintype "passive"))
      (node (ref "R429") (pin "2") (pinfunction "2_2") (pintype "passive"))
      (node (ref "U407") (pin "5") (pinfunction "OUT_5") (pintype "passive"))
    )
    (net (code "25") (name "M15V") (class "Default")
      (node (ref "C428") (pin "2") (pinfunction "2_2") (pintype "passive"))
      (node (ref "C431") (pin "2") (pinfunction "2_2") (pintype "passive"))
      (node (ref "C432") (pin "1") (pinfunction "1_1") (pintype "passive"))
      (node (ref "C451") (pin "2") (pinfunction "2_2") (pintype "passive"))
      (node (ref "C452") (pin "2") (pinfunction "2_2") (pintype "passive"))
      (node (ref "D401") (pin "1") (pinfunction "1_1") (pintype "passive"))
      (node (ref "R416") (pin "1") (pinfunction "1_1") (pintype "passive"))
      (node (ref "U402") (pin "4") (pinfunction "GND_4") (pintype "passive"))
      (node (ref "U407") (pin "2") (pinfunction "IN_2") (pintype "passive"))
      (node (ref "U407") (pin "3") (pinfunction "~{SHDN}_3") (pintype "passive"))
      (node (ref "U408") (pin "2") (pinfunction "IN_2") (pintype "passive"))
      (node (ref "U408") (pin "3") (pinfunction "~{SHDN}_3") (pintype "passive"))
    )
    (net (code "26") (name "Net-(BAT-Pad1)") (class "Default")
      (node (ref "BAT") (pin "1") (pinfunction "1_1") (pintype "passive"))
      (node (ref "C400") (pin "1") (pinfunction "1_1") (pintype "passive"))
      (node (ref "U400") (pin "34") (pinfunction "BAT_34") (pintype "passive"))
      (node (ref "U400") (pin "35") (pinfunction "BAT_35") (pintype "passive"))
    )
    (net (code "27") (name "Net-(C402-Pad1)") (class "Default")
      (node (ref "C402") (pin "1") (pinfunction "1_1") (pintype "passive"))
      (node (ref "R400") (pin "2") (pinfunction "2_2") (pintype "passive"))
    )
    (net (code "28") (name "Net-(U400-BIAS)") (class "Default")
      (node (ref "R410") (pin "1") (pinfunction "1_1") (pintype "passive"))
      (node (ref "U400") (pin "24") (pinfunction "BIAS_24") (pintype "passive"))
    )
    (net (code "29") (name "Net-(U400-CHGLED)") (class "Default")
      (node (ref "R411") (pin "1") (pinfunction "1_1") (pintype "passive"))
      (node (ref "U400") (pin "36") (pinfunction "CHGLED_36") (pintype "passive"))
    )
    (net (code "30") (name "Net-(U400-GPIO0{slash}LDOio0)") (class "Default")
      (node (ref "C403") (pin "2") (pinfunction "2_2") (pintype "passive"))
      (node (ref "U400") (pin "19") (pinfunction "GPIO0/LDOio0_19") (pintype "passive"))
    )
    (net (code "31") (name "Net-(U400-LDOIN)") (class "Default")
      (node (ref "C407") (pin "1") (pinfunction "1_1") (pintype "passive"))
      (node (ref "R401") (pin "1") (pinfunction "1_1") (pintype "passive"))
      (node (ref "U400") (pin "13") (pinfunction "LDOIN_13") (pintype "passive"))
    )
    (net (code "32") (name "Net-(U400-LX1)") (class "Default")
      (node (ref "L400") (pin "1") (pinfunction "1_1") (pintype "passive"))
      (node (ref "U400") (pin "45") (pinfunction "LX1_45") (pintype "passive"))
    )
    (net (code "33") (name "Net-(U400-LX2)") (class "Default")
      (node (ref "L401") (pin "1") (pinfunction "1_1") (pintype "passive"))
      (node (ref "U400") (pin "8") (pinfunction "LX2_8") (pintype "passive"))
    )
    (net (code "34") (name "Net-(U400-LX3)") (class "Default")
      (node (ref "L402") (pin "1") (pinfunction "1_1") (pintype "passive"))
      (node (ref "U400") (pin "15") (pinfunction "LX3_15") (pintype "passive"))
    )
    (net (code "35") (name "Net-(U400-PWRON)") (class "Default")
      (node (ref "C418") (pin "1") (pinfunction "1_1") (pintype "passive"))
      (node (ref "R409") (pin "1") (pinfunction "1_1") (pintype "passive"))
      (node (ref "U400") (pin "23") (pinfunction "PWRON_23") (pintype "passive"))
    )
    (net (code "36") (name "Net-(U400-TS)") (class "Default")
      (node (ref "BAT") (pin "2") (pinfunction "2_2") (pintype "passive"))
      (node (ref "U400") (pin "37") (pinfunction "TS_37") (pintype "passive"))
    )
    (net (code "37") (name "Net-(U400-VBUS)") (class "Default")
      (node (ref "R400") (pin "1") (pinfunction "1_1") (pintype "passive"))
      (node (ref "U400") (pin "31") (pinfunction "VBUS_31") (pintype "passive"))
      (node (ref "USB") (pin "1") (pinfunction "VBUS_1") (pintype "passive"))
    )
    (net (code "38") (name "Net-(U400-VINT)") (class "Default")
      (node (ref "C415") (pin "1") (pinfunction "1_1") (pintype "passive"))
      (node (ref "U400") (pin "26") (pinfunction "VINT_26") (pintype "passive"))
    )
    (net (code "39") (name "Net-(U400-VREF)") (class "Default")
      (node (ref "C417") (pin "1") (pinfunction "1_1") (pintype "passive"))
      (node (ref "U400") (pin "25") (pinfunction "VREF_25") (pintype "passive"))
    )
    (net (code "40") (name "Net-(U401-CII)") (class "Default")
      (node (ref "R412") (pin "2") (pinfunction "2_2") (pintype "passive"))
      (node (ref "R413") (pin "2") (pinfunction "2_2") (pintype "passive"))
      (node (ref "U401") (pin "5") (pinfunction "CII_5") (pintype "passive"))
    )
    (net (code "41") (name "Net-(U401-IS)") (class "Default")
      (node (ref "L403") (pin "1") (pinfunction "1_1") (pintype "passive"))
      (node (ref "R414") (pin "1") (pinfunction "1_1") (pintype "passive"))
      (node (ref "R424") (pin "1") (pinfunction "1_1") (pintype "passive"))
      (node (ref "U401") (pin "7") (pinfunction "IS_7") (pintype "passive"))
    )
    (net (code "42") (name "Net-(U401-ON{slash}~{OFF})") (class "Default")
      (node (ref "R424") (pin "2") (pinfunction "2_2") (pintype "passive"))
      (node (ref "U401") (pin "8") (pinfunction "ON/~{OFF}_8") (pintype "passive"))
    )
    (net (code "43") (name "Net-(U401-SC)") (class "Default")
      (node (ref "D400") (pin "1") (pinfunction "1_1") (pintype "passive"))
      (node (ref "L403") (pin "2") (pinfunction "2_2") (pintype "passive"))
      (node (ref "U401") (pin "1") (pinfunction "SC_1") (pintype "passive"))
    )
    (net (code "44") (name "Net-(U401-TC)") (class "Default")
      (node (ref "C425") (pin "2") (pinfunction "2_2") (pintype "passive"))
      (node (ref "U401") (pin "3") (pinfunction "TC_3") (pintype "passive"))
    )
    (net (code "45") (name "Net-(U402-CII)") (class "Default")
      (node (ref "R416") (pin "2") (pinfunction "2_2") (pintype "passive"))
      (node (ref "R417") (pin "1") (pinfunction "1_1") (pintype "passive"))
      (node (ref "U402") (pin "5") (pinfunction "CII_5") (pintype "passive"))
    )
    (net (code "46") (name "Net-(U402-IS)") (class "Default")
      (node (ref "R415") (pin "2") (pinfunction "2_2") (pintype "passive"))
      (node (ref "U402") (pin "1") (pinfunction "SC_1") (pintype "passive"))
      (node (ref "U402") (pin "7") (pinfunction "IS_7") (pintype "passive"))
      (node (ref "U402") (pin "8") (pinfunction "ON/~{OFF}_8") (pintype "passive"))
    )
    (net (code "47") (name "Net-(U402-SE)") (class "Default")
      (node (ref "D401") (pin "2") (pinfunction "2_2") (pintype "passive"))
      (node (ref "L404") (pin "1") (pinfunction "1_1") (pintype "passive"))
      (node (ref "U402") (pin "2") (pinfunction "SE_2") (pintype "passive"))
    )
    (net (code "48") (name "Net-(U402-TC)") (class "Default")
      (node (ref "C432") (pin "2") (pinfunction "2_2") (pintype "passive"))
      (node (ref "U402") (pin "3") (pinfunction "TC_3") (pintype "passive"))
    )
    (net (code "49") (name "Net-(U403-ADJ)") (class "Default")
      (node (ref "C447") (pin "2") (pinfunction "2_2") (pintype "passive"))
      (node (ref "R418") (pin "2") (pinfunction "2_2") (pintype "passive"))
      (node (ref "R419") (pin "1") (pinfunction "1_1") (pintype "passive"))
      (node (ref "U403") (pin "2") (pinfunction "ADJ_2") (pintype "passive"))
    )
    (net (code "50") (name "Net-(U403-BYP)") (class "Default")
      (node (ref "C434") (pin "2") (pinfunction "2_2") (pintype "passive"))
      (node (ref "U403") (pin "3") (pinfunction "BYP_3") (pintype "passive"))
    )
    (net (code "51") (name "Net-(U404-ADJ)") (class "Default")
      (node (ref "C448") (pin "2") (pinfunction "2_2") (pintype "passive"))
      (node (ref "R420") (pin "2") (pinfunction "2_2") (pintype "passive"))
      (node (ref "R421") (pin "1") (pinfunction "1_1") (pintype "passive"))
      (node (ref "U404") (pin "2") (pinfunction "ADJ_2") (pintype "passive"))
    )
    (net (code "52") (name "Net-(U404-BYP)") (class "Default")
      (node (ref "C438") (pin "1") (pinfunction "1_1") (pintype "passive"))
      (node (ref "U404") (pin "3") (pinfunction "BYP_3") (pintype "passive"))
    )
    (net (code "53") (name "Net-(U405-ADJ)") (class "Default")
      (node (ref "C449") (pin "2") (pinfunction "2_2") (pintype "passive"))
      (node (ref "R422") (pin "2") (pinfunction "2_2") (pintype "passive"))
      (node (ref "R423") (pin "1") (pinfunction "1_1") (pintype "passive"))
      (node (ref "U405") (pin "2") (pinfunction "ADJ_2") (pintype "passive"))
    )
    (net (code "54") (name "Net-(U405-BYP)") (class "Default")
      (node (ref "C441") (pin "2") (pinfunction "2_2") (pintype "passive"))
      (node (ref "U405") (pin "3") (pinfunction "BYP_3") (pintype "passive"))
    )
    (net (code "55") (name "Net-(U406-CII)") (class "Default")
      (node (ref "R427") (pin "2") (pinfunction "2_2") (pintype "passive"))
      (node (ref "R428") (pin "2") (pinfunction "2_2") (pintype "passive"))
      (node (ref "U406") (pin "5") (pinfunction "CII_5") (pintype "passive"))
    )
    (net (code "56") (name "Net-(U406-IS)") (class "Default")
      (node (ref "L405") (pin "1") (pinfunction "1_1") (pintype "passive"))
      (node (ref "R425") (pin "1") (pinfunction "1_1") (pintype "passive"))
      (node (ref "R426") (pin "2") (pinfunction "2_2") (pintype "passive"))
      (node (ref "U406") (pin "7") (pinfunction "IS_7") (pintype "passive"))
    )
    (net (code "57") (name "Net-(U406-ON{slash}~{OFF})") (class "Default")
      (node (ref "R425") (pin "2") (pinfunction "2_2") (pintype "passive"))
      (node (ref "U406") (pin "8") (pinfunction "ON/~{OFF}_8") (pintype "passive"))
    )
    (net (code "58") (name "Net-(U406-SC)") (class "Default")
      (node (ref "D405") (pin "1") (pinfunction "1_1") (pintype "passive"))
      (node (ref "L405") (pin "2") (pinfunction "2_2") (pintype "passive"))
      (node (ref "U406") (pin "1") (pinfunction "SC_1") (pintype "passive"))
    )
    (net (code "59") (name "Net-(U406-TC)") (class "Default")
      (node (ref "C443") (pin "1") (pinfunction "1_1") (pintype "passive"))
      (node (ref "U406") (pin "3") (pinfunction "TC_3") (pintype "passive"))
    )
    (net (code "60") (name "Net-(U407-ADJ)") (class "Default")
      (node (ref "R429") (pin "1") (pinfunction "1_1") (pintype "passive"))
      (node (ref "R430") (pin "1") (pinfunction "1_1") (pintype "passive"))
      (node (ref "U407") (pin "4") (pinfunction "ADJ_4") (pintype "passive"))
    )
    (net (code "61") (name "Net-(U408-ADJ)") (class "Default")
      (node (ref "R431") (pin "2") (pinfunction "2_2") (pintype "passive"))
      (node (ref "R432") (pin "1") (pinfunction "1_1") (pintype "passive"))
      (node (ref "U408") (pin "4") (pinfunction "ADJ_4") (pintype "passive"))
    )
    (net (code "62") (name "VCCIO") (class "Default")
      (node (ref "R402") (pin "2") (pinfunction "2_2") (pintype "passive"))
      (node (ref "R403") (pin "2") (pinfunction "2_2") (pintype "passive"))
      (node (ref "R404") (pin "2") (pinfunction "2_2") (pintype "passive"))
      (node (ref "U400") (pin "6") (pinfunction "N_VBUSEN_6") (pintype "passive"))
    )
    (net (code "63") (name "unconnected-(U400-ACIN-Pad32)") (class "Default")
      (node (ref "U400") (pin "32") (pinfunction "ACIN_32") (pintype "passive"))
    )
    (net (code "64") (name "unconnected-(U400-ACIN-Pad33)") (class "Default")
      (node (ref "U400") (pin "33") (pinfunction "ACIN_33") (pintype "passive"))
    )
    (net (code "65") (name "unconnected-(U400-BACKUP-Pad30)") (class "Default")
      (node (ref "U400") (pin "30") (pinfunction "BACKUP_30") (pintype "passive"))
    )
    (net (code "66") (name "unconnected-(U400-GPIO1-Pad18)") (class "Default")
      (node (ref "U400") (pin "18") (pinfunction "GPIO1_18") (pintype "passive"))
    )
    (net (code "67") (name "unconnected-(U400-GPIO2-Pad20)") (class "Default")
      (node (ref "U400") (pin "20") (pinfunction "GPIO2_20") (pintype "passive"))
    )
    (net (code "68") (name "unconnected-(U400-GPIO3-Pad41)") (class "Default")
      (node (ref "U400") (pin "41") (pinfunction "GPIO3_41") (pintype "passive"))
    )
    (net (code "69") (name "unconnected-(U400-GPIO4-Pad42)") (class "Default")
      (node (ref "U400") (pin "42") (pinfunction "GPIO4_42") (pintype "passive"))
    )
    (net (code "70") (name "unconnected-(U400-NC-Pad43)") (class "Default")
      (node (ref "U400") (pin "43") (pinfunction "NC_43") (pintype "passive"))
    )
    (net (code "71") (name "unconnected-(U403-NC-Pad6)") (class "Default")
      (node (ref "U403") (pin "6") (pinfunction "NC_6") (pintype "passive"))
    )
    (net (code "72") (name "unconnected-(U403-NC-Pad7)") (class "Default")
      (node (ref "U403") (pin "7") (pinfunction "NC_7") (pintype "passive"))
    )
    (net (code "73") (name "unconnected-(U404-NC-Pad6)") (class "Default")
      (node (ref "U404") (pin "6") (pinfunction "NC_6") (pintype "passive"))
    )
    (net (code "74") (name "unconnected-(U404-NC-Pad7)") (class "Default")
      (node (ref "U404") (pin "7") (pinfunction "NC_7") (pintype "passive"))
    )
    (net (code "75") (name "unconnected-(U405-NC-Pad6)") (class "Default")
      (node (ref "U405") (pin "6") (pinfunction "NC_6") (pintype "passive"))
    )
    (net (code "76") (name "unconnected-(U405-NC-Pad7)") (class "Default")
      (node (ref "U405") (pin "7") (pinfunction "NC_7") (pintype "passive"))
    )
    (net (code "77") (name "unconnected-(U409-NC-Pad4)") (class "Default")
      (node (ref "U409") (pin "4") (pinfunction "NC_4") (pintype "passive"))
    )
    (net (code "78") (name "unconnected-(USB-D+-Pad3)") (class "Default")
      (node (ref "USB") (pin "3") (pinfunction "D+_3") (pintype "bidirectional"))
    )
    (net (code "79") (name "unconnected-(USB-D--Pad2)") (class "Default")
      (node (ref "USB") (pin "2") (pinfunction "D-_2") (pintype "bidirectional"))
    )
    (net (code "80") (name "unconnected-(USB-ID-Pad4)") (class "Default")
      (node (ref "USB") (pin "4") (pinfunction "ID_4") (pintype "passive"))
    )
  )
)
